# MotorPhase.net
KiCad netlist of a schematic drawn in Altium Designer
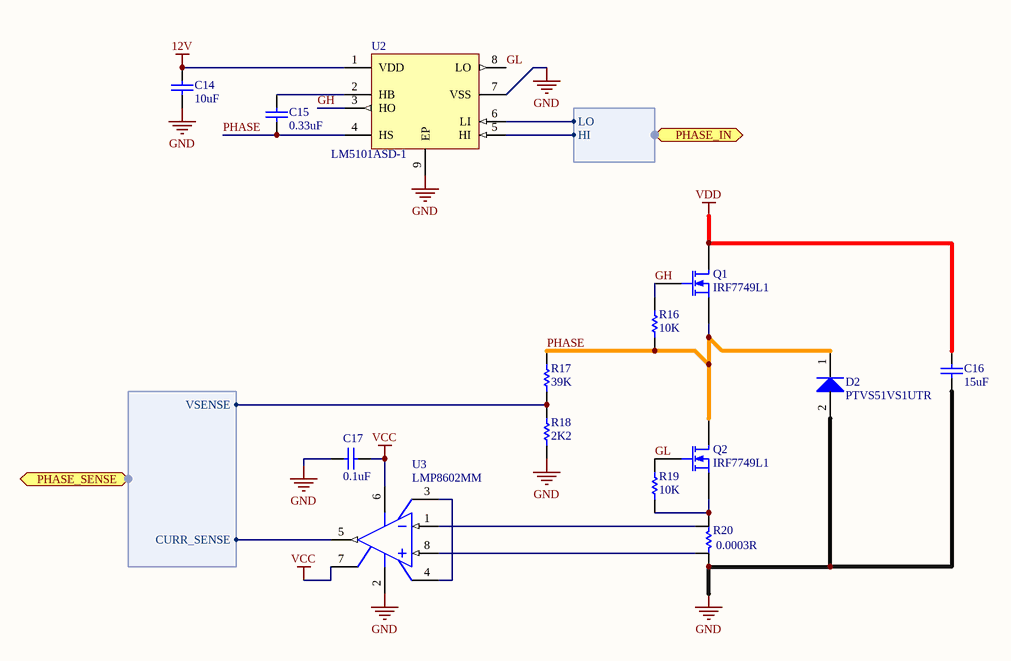
[diagram p0: MotorPhase.SchDoc]

(export (version "E")
  (design (tool "Eeschema 10.0.6"))
  (components
    (comp (ref "C14")
      (value "10uF")
      (footprint "C0603[1608X92]")
      (description "10uF 16V 10% 0603 (1608 Metric)")
      (fields (field (name "TOLERANCE") "10%") (field (name "PARTNUMBER") "GRM188R61C106KAALD"))
      (libsource (lib "Capacitors") (part "CAP_10uF_16V_0603_10%"))
    )
    (comp (ref "C15")
      (value "0.33uF")
      (footprint "C0603[1608X92]")
      (description "0.33uF 25V 10% 0603 (1608 Metric)")
      (fields (field (name "TOLERANCE") "10%") (field (name "PARTNUMBER") "GCJ188R91E334KA01D"))
      (libsource (lib "Capacitors") (part "CAP_0.33uF_25V_0603_10%"))
    )
    (comp (ref "C16")
      (value "15uF")
      (footprint "C2220[5750X230]")
      (description "15uF 100V 20% 2220 (5750 Metric)")
      (fields (field (name "TOLERANCE") "20%") (field (name "PARTNUMBER") "C5750X7S2A156M250KB"))
      (libsource (lib "Capacitors") (part "CAP_15uF_100V_2220_20%"))
    )
    (comp (ref "C17")
      (value "0.1uF")
      (footprint "C0402[1005X55]")
      (description "0.1uF 6.3V 10% 0402 (1005 Metric)")
      (fields (field (name "TOLERANCE") "10%") (field (name "PARTNUMBER") "GRM155R70J104KA01D"))
      (libsource (lib "Capacitors") (part "CAP_0.1uF_6.3V_0402_10%"))
    )
    (comp (ref "D2")
      (value "PTVS51VS1UTR")
      (footprint "SOD-123W")
      (fields (field (name "PARTNUMBER") "PTVS51VS1UTR,115") (field (name "MANUFACTURER") "NXP"))
      (libsource (lib "Diodes") (part "PTVS51VS1UTR,115"))
    )
    (comp (ref "Q1")
      (value "IRF7749L1")
      (footprint "DIRECTFET-9")
      (description "N-Channel MOSFET")
      (fields
        (field (name "PARTNUMBER") "IRF7749L1TRPBF")
        (field (name "MANUFACTURER") "Infineon Technologies")
      )
      (libsource (lib "MOSFETs") (part "IRF7749L2"))
    )
    (comp (ref "Q2")
      (value "IRF7749L1")
      (footprint "DIRECTFET-9")
      (description "N-Channel MOSFET")
      (fields
        (field (name "PARTNUMBER") "IRF7749L1TRPBF")
        (field (name "MANUFACTURER") "Infineon Technologies")
      )
      (libsource (lib "MOSFETs") (part "IRF7749L2"))
    )
    (comp (ref "R16")
      (value "10K")
      (footprint "R0402[1005]")
      (description "10K 0.063W 1% 0402 (1005 Metric)")
      (fields (field (name "TOLERANCE") "1%") (field (name "POWER") "0.063W"))
      (libsource (lib "Resistors") (part "RES_10K_0402_1%"))
    )
    (comp (ref "R17")
      (value "39K")
      (footprint "R0402[1005]")
      (description "39K 0.063W 1% 0402 (1005 Metric)")
      (fields (field (name "TOLERANCE") "1%") (field (name "POWER") "0.063W"))
      (libsource (lib "Resistors") (part "RES_39K_0402_1%"))
    )
    (comp (ref "R18")
      (value "2K2")
      (footprint "R0402[1005]")
      (description "2K2 0.063W 1% 0402 (1005 Metric)")
      (fields (field (name "TOLERANCE") "1%") (field (name "POWER") "0.063W"))
      (libsource (lib "Resistors") (part "RES_2K2_0402_1%"))
    )
    (comp (ref "R19")
      (value "10K")
      (footprint "R0402[1005]")
      (description "10K 0.063W 1% 0402 (1005 Metric)")
      (fields (field (name "TOLERANCE") "1%") (field (name "POWER") "0.063W"))
      (libsource (lib "Resistors") (part "RES_10K_0402_1%"))
    )
    (comp (ref "R20")
      (value "0.0003R")
      (footprint "WSL2726")
      (description "Current Sense Resistor, 0.0003R 1%")
      (fields (field (name "PARTNUMBER") "WSL2726L3000FEB") (field (name "POWER") "3W"))
      (libsource (lib "Components") (part "WSL27261L000FEB"))
    )
    (comp (ref "U2")
      (value "LM5101ASD-1")
      (footprint "DFN8")
      (fields (field (name "MANUFACTURER") "Texas Instruments"))
      (libsource (lib "ICs") (part "LM5101ASD-1"))
    )
    (comp (ref "U3")
      (value "LMP8602MM")
      (footprint "MUA08A_L")
      (fields (field (name "MANUFACTURER") "Texas Instruments"))
      (libsource (lib "Altium Content Vault") (part "CMP-0055-01489-1"))
    )
  )
  (nets
    (net (code "4") (name "/CURR_SENSE") (class "Default")
      (node (ref "U3") (pin "5") (pinfunction "OUT_5") (pintype "output"))
    )
    (net (code "5") (name "/GH") (class "Default")
      (node (ref "Q1") (pin "1") (pinfunction "G_1") (pintype "passive"))
      (node (ref "R16") (pin "2") (pinfunction "2_2") (pintype "passive"))
      (node (ref "U2") (pin "3") (pinfunction "HO_3") (pintype "output"))
    )
    (net (code "6") (name "/GL") (class "Default")
      (node (ref "Q2") (pin "1") (pinfunction "G_1") (pintype "passive"))
      (node (ref "R19") (pin "2") (pinfunction "2_2") (pintype "passive"))
      (node (ref "U2") (pin "8") (pinfunction "LO_8") (pintype "output"))
    )
    (net (code "7") (name "/HI") (class "Default")
      (node (ref "U2") (pin "5") (pinfunction "HI_5") (pintype "input"))
    )
    (net (code "8") (name "/LO") (class "Default")
      (node (ref "U2") (pin "6") (pinfunction "LI_6") (pintype "input"))
    )
    (net (code "9") (name "/PHASE") (class "Default")
      (node (ref "C15") (pin "1") (pinfunction "1_1") (pintype "passive"))
      (node (ref "D2") (pin "1") (pinfunction "K_1") (pintype "passive"))
      (node (ref "Q1") (pin "2") (pinfunction "S_2") (pintype "passive"))
      (node (ref "Q2") (pin "3") (pinfunction "D_3") (pintype "passive"))
      (node (ref "R16") (pin "1") (pinfunction "1_1") (pintype "passive"))
      (node (ref "R17") (pin "2") (pinfunction "2_2") (pintype "passive"))
      (node (ref "U2") (pin "4") (pinfunction "HS_4") (pintype "passive"))
    )
    (net (code "10") (name "/VSENSE") (class "Default")
      (node (ref "R17") (pin "1") (pinfunction "1_1") (pintype "passive"))
      (node (ref "R18") (pin "2") (pinfunction "2_2") (pintype "passive"))
    )
    (net (code "13") (name "12V") (class "Default")
      (node (ref "C14") (pin "2") (pinfunction "2_2") (pintype "passive"))
      (node (ref "U2") (pin "1") (pinfunction "VDD_1") (pintype "power_in"))
    )
    (net (code "14") (name "GND") (class "Default")
      (node (ref "C14") (pin "1") (pinfunction "1_1") (pintype "passive"))
      (node (ref "C16") (pin "1") (pinfunction "1_1") (pintype "passive"))
      (node (ref "C17") (pin "2") (pinfunction "2_2") (pintype "passive"))
      (node (ref "D2") (pin "2") (pinfunction "A_2") (pintype "passive"))
      (node (ref "R18") (pin "1") (pinfunction "1_1") (pintype "passive"))
      (node (ref "R20") (pin "1") (pinfunction "1_1") (pintype "passive"))
      (node (ref "U2") (pin "7") (pinfunction "VSS_7") (pintype "power_in"))
      (node (ref "U2") (pin "9") (pinfunction "EP_9") (pintype "power_in"))
      (node (ref "U3") (pin "2") (pinfunction "GND_2") (pintype "power_in"))
    )
    (net (code "15") (name "Net-(Q2-S)") (class "Default")
      (node (ref "Q2") (pin "2") (pinfunction "S_2") (pintype "passive"))
      (node (ref "R19") (pin "1") (pinfunction "1_1") (pintype "passive"))
      (node (ref "R20") (pin "2") (pinfunction "2_2") (pintype "passive"))
    )
    (net (code "16") (name "Net-(U2-HB)") (class "Default")
      (node (ref "C15") (pin "2") (pinfunction "2_2") (pintype "passive"))
      (node (ref "U2") (pin "2") (pinfunction "HB_2") (pintype "passive"))
    )
    (net (code "17") (name "Net-(U3-A1)") (class "Default")
      (node (ref "U3") (pin "3") (pinfunction "A1_3") (pintype "passive"))
      (node (ref "U3") (pin "4") (pinfunction "A2_4") (pintype "passive"))
    )
    (net (code "18") (name "Net-(U3-IN+)") (class "Default")
      (node (ref "R20") (pin "3") (pinfunction "3_3") (pintype "passive"))
      (node (ref "U3") (pin "8") (pinfunction "IN+_8") (pintype "input"))
    )
    (net (code "19") (name "Net-(U3-IN-)") (class "Default")
      (node (ref "R20") (pin "4") (pinfunction "4_4") (pintype "passive"))
      (node (ref "U3") (pin "1") (pinfunction "IN-_1") (pintype "input"))
    )
    (net (code "20") (name "VCC") (class "Default")
      (node (ref "C17") (pin "1") (pinfunction "1_1") (pintype "passive"))
      (node (ref "U3") (pin "6") (pinfunction "VS_6") (pintype "power_in"))
      (node (ref "U3") (pin "7") (pinfunction "OFS_7") (pintype "passive"))
    )
    (net (code "21") (name "VDD") (class "Default")
      (node (ref "C16") (pin "2") (pinfunction "2_2") (pintype "passive"))
      (node (ref "Q1") (pin "3") (pinfunction "D_3") (pintype "passive"))
    )
  )
)
